# porcupine4v1_7.net
KiCad netlist of a schematic drawn in EAGLE
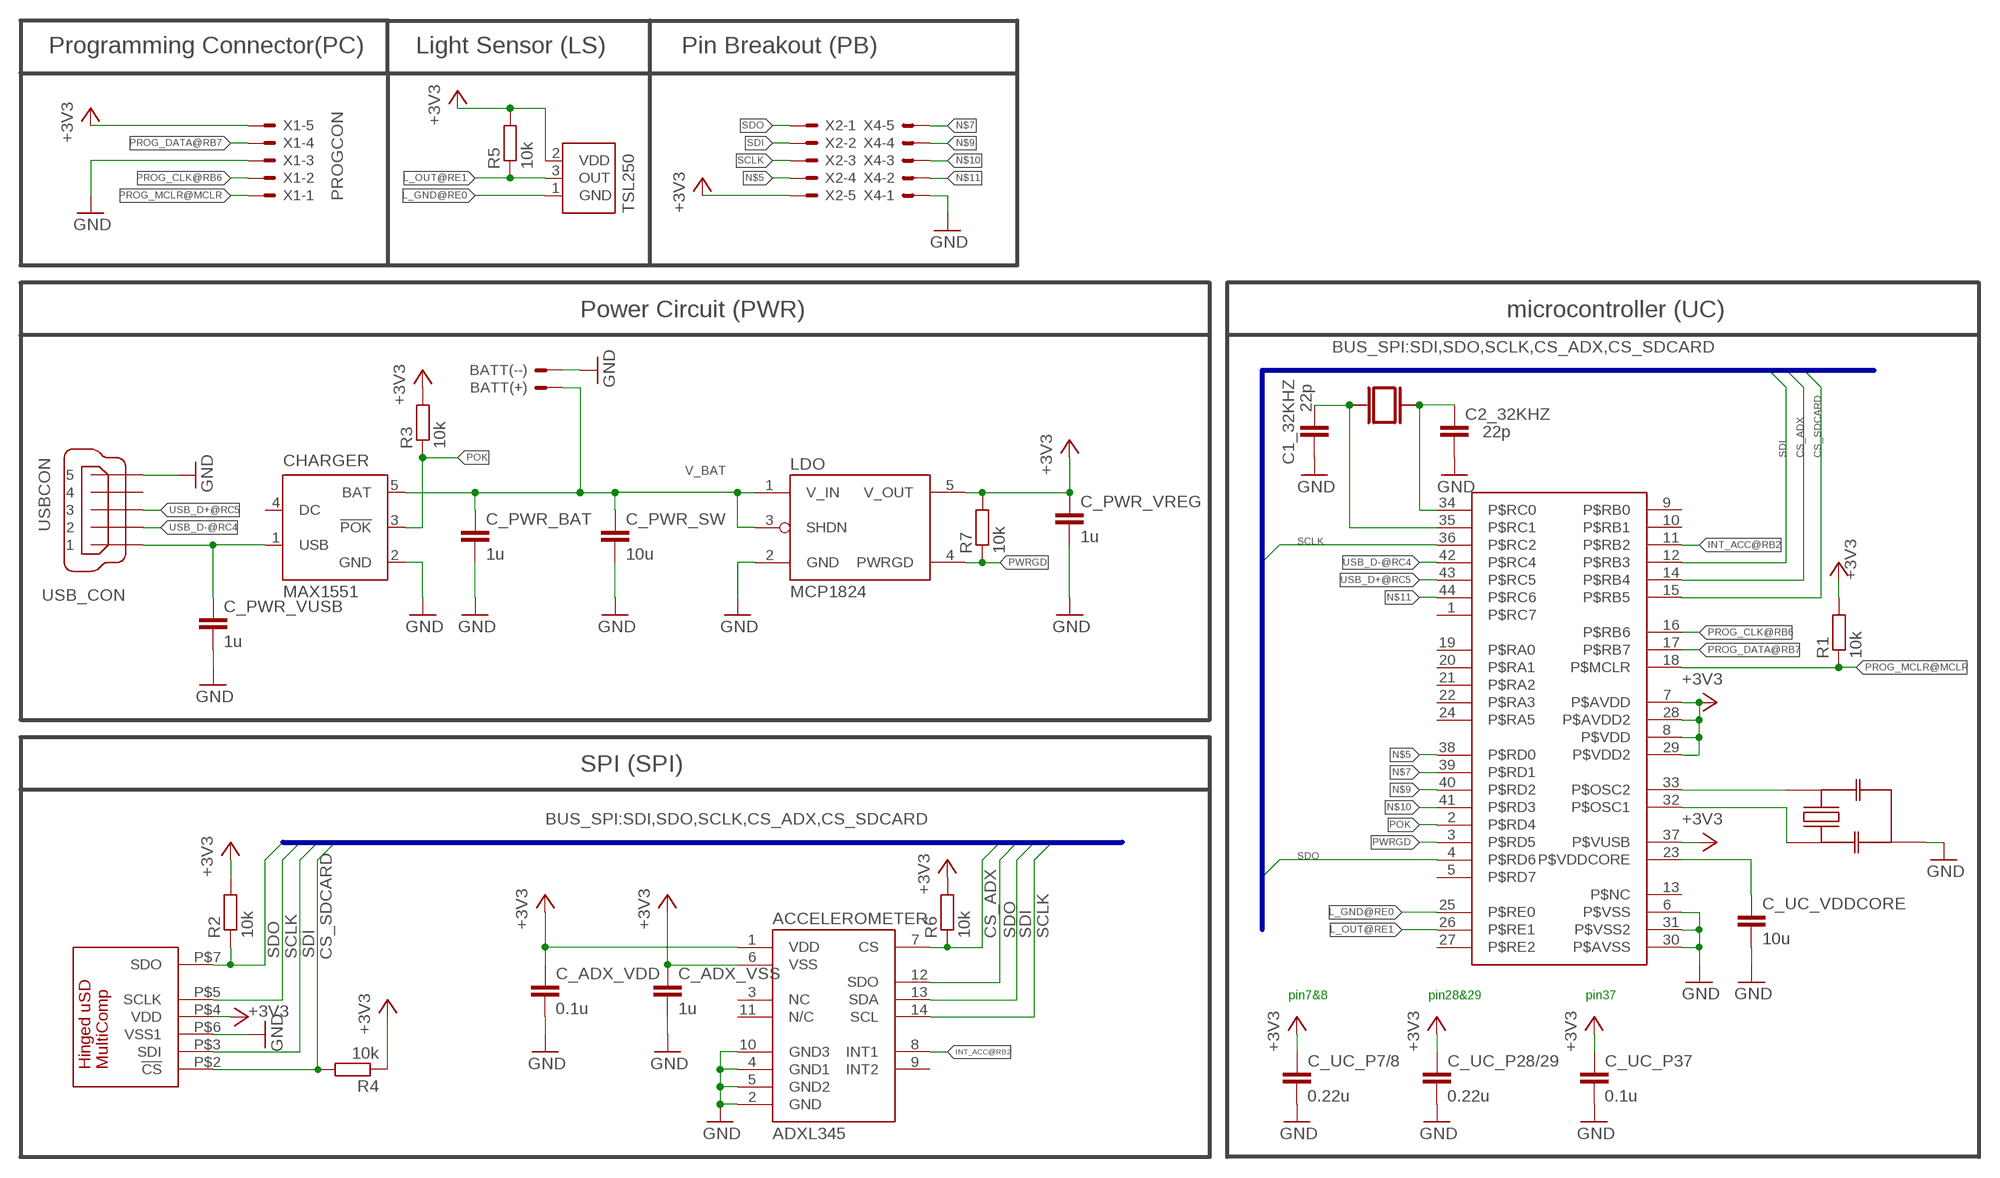
[diagram p0: schematic, sheet 1]

(export (version "E")
  (design (tool "Eeschema 10.0.6"))
  (components
    (comp (ref "12MHZ_RESONATOR")
      (value "RESONATORPRQC-S")
      (footprint "eagle-import:PRQC")
      (fields
        (field (name "DIGIKEY") "http://www.digikey.com/product-detail/en/PRQC12.00CR5010X000/478-6318-1-ND/2506334")
      )
      (libsource (lib "eagle-import") (part "RESONATORPRQC-S"))
    )
    (comp (ref "32KHZ_CRYSTAL")
      (value "SMD_CRYSTAL")
      (footprint "eagle-import:SMD_CRYSTAL")
      (libsource (lib "eagle-import") (part "SMD_CRYSTAL"))
    )
    (comp (ref "ACCELEROMETER")
      (value "ADXL345")
      (footprint "eagle-import:LGA14")
      (libsource (lib "eagle-import") (part "ADXL345"))
    )
    (comp (ref "BATT")
      (value "LI-ION-PACK")
      (footprint "eagle-import:LI-ION-CONNECT")
      (libsource (lib "eagle-import") (part "LI-ION-PACK"))
    )
    (comp (ref "C1_32KHZ")
      (value "22p")
      (footprint "eagle-import:C0603K")
      (libsource (lib "eagle-import") (part "C-EUC0603K"))
    )
    (comp (ref "C2_32KHZ")
      (value "22p")
      (footprint "eagle-import:C0603K")
      (libsource (lib "eagle-import") (part "C-EUC0603K"))
    )
    (comp (ref "CHARGER")
      (value "MAX1551")
      (footprint "eagle-import:SOT23-5L")
      (fields (field (name "MF") "MAXIM") (field (name "MPN") "MAX1551EZK-T"))
      (libsource (lib "eagle-import") (part "MAX1551"))
    )
    (comp (ref "C_ADX_VDD")
      (value "0.1u")
      (footprint "eagle-import:C0603K")
      (libsource (lib "eagle-import") (part "C-EUC0603K"))
    )
    (comp (ref "C_ADX_VSS")
      (value "1u")
      (footprint "eagle-import:C0603K")
      (libsource (lib "eagle-import") (part "C-EUC0603K"))
    )
    (comp (ref "C_PWR_BAT")
      (value "1u")
      (footprint "eagle-import:C0603K")
      (libsource (lib "eagle-import") (part "C-EUC0603K"))
    )
    (comp (ref "C_PWR_SW")
      (value "10u")
      (footprint "eagle-import:C0805K")
      (libsource (lib "eagle-import") (part "C-EUC0805K"))
    )
    (comp (ref "C_PWR_VREG")
      (value "1u")
      (footprint "eagle-import:C0603K")
      (libsource (lib "eagle-import") (part "C-EUC0603K"))
    )
    (comp (ref "C_PWR_VUSB")
      (value "1u")
      (footprint "eagle-import:C0603K")
      (libsource (lib "eagle-import") (part "C-EUC0603K"))
    )
    (comp (ref "C_UC_P7/8")
      (value "0.22u")
      (footprint "eagle-import:C0603K")
      (libsource (lib "eagle-import") (part "C-EUC0603K"))
    )
    (comp (ref "C_UC_P28/29")
      (value "0.22u")
      (footprint "eagle-import:C0603K")
      (libsource (lib "eagle-import") (part "C-EUC0603K"))
    )
    (comp (ref "C_UC_P37")
      (value "0.1u")
      (footprint "eagle-import:C0603K")
      (libsource (lib "eagle-import") (part "C-EUC0603K"))
    )
    (comp (ref "C_UC_VDDCORE")
      (value "10u")
      (footprint "eagle-import:C0805K")
      (libsource (lib "eagle-import") (part "C-EUC0805K"))
    )
    (comp (ref "LDO")
      (value "MCP1824")
      (footprint "eagle-import:SOT-23-5")
      (libsource (lib "eagle-import") (part "MCP1824"))
    )
    (comp (ref "LIGHTSENSE")
      (value "TSL250")
      (footprint "eagle-import:TSL")
      (libsource (lib "eagle-import") (part "TSL250"))
    )
    (comp (ref "PIC_CONTROLLER")
      (value "PIC_P2V6")
      (footprint "eagle-import:QFN44ML8X8")
      (libsource (lib "eagle-import") (part "PIC_P2V6"))
    )
    (comp (ref "R1")
      (value "10k")
      (footprint "eagle-import:R0603")
      (libsource (lib "eagle-import") (part "R-EU_R0603"))
    )
    (comp (ref "R2")
      (value "10k")
      (footprint "eagle-import:R0603")
      (libsource (lib "eagle-import") (part "R-EU_R0603"))
    )
    (comp (ref "R3")
      (value "10k")
      (footprint "eagle-import:R0603")
      (libsource (lib "eagle-import") (part "R-EU_R0603"))
    )
    (comp (ref "R4")
      (value "10k")
      (footprint "eagle-import:R0603")
      (libsource (lib "eagle-import") (part "R-EU_R0603"))
    )
    (comp (ref "R5")
      (value "10k")
      (footprint "eagle-import:R0603")
      (libsource (lib "eagle-import") (part "R-EU_R0603"))
    )
    (comp (ref "R6")
      (value "10k")
      (footprint "eagle-import:R0603")
      (libsource (lib "eagle-import") (part "R-EU_R0603"))
    )
    (comp (ref "R7")
      (value "10k")
      (footprint "eagle-import:R0603")
      (libsource (lib "eagle-import") (part "R-EU_R0603"))
    )
    (comp (ref "SDCARD_CON")
      (value "MICROSD_CONN")
      (footprint "eagle-import:460DA40013")
      (libsource (lib "eagle-import") (part "MICROSD_CONN"))
    )
    (comp (ref "USB_CON")
      (value "USBCON")
      (footprint "eagle-import:248601")
      (libsource (lib "eagle-import") (part "USBCON"))
    )
    (comp (ref "X1")
      (value "PROGCON")
      (footprint "eagle-import:53047-05-OCT")
      (libsource (lib "eagle-import") (part "PROGCON"))
    )
    (comp (ref "X2")
      (value "PROGCON")
      (footprint "eagle-import:53047-05-OCT")
      (libsource (lib "eagle-import") (part "PROGCON"))
    )
    (comp (ref "X4")
      (value "PROGCON")
      (footprint "eagle-import:53047-05-OCT")
      (libsource (lib "eagle-import") (part "PROGCON"))
    )
  )
  (nets
    (net (code "2") (name "+3V3") (class "Default")
      (node (ref "ACCELEROMETER") (pin "1") (pinfunction "VDD_1") (pintype "bidirectional"))
      (node (ref "ACCELEROMETER") (pin "6") (pinfunction "VSS_6") (pintype "bidirectional"))
      (node (ref "C_ADX_VDD") (pin "1") (pinfunction "1_1") (pintype "passive"))
      (node (ref "C_ADX_VSS") (pin "1") (pinfunction "1_1") (pintype "passive"))
      (node (ref "C_PWR_VREG") (pin "1") (pinfunction "1_1") (pintype "passive"))
      (node (ref "C_UC_P28/29") (pin "1") (pinfunction "1_1") (pintype "passive"))
      (node (ref "C_UC_P37") (pin "1") (pinfunction "1_1") (pintype "passive"))
      (node (ref "C_UC_P7/8") (pin "1") (pinfunction "1_1") (pintype "passive"))
      (node (ref "LDO") (pin "5") (pinfunction "V_OUT_5") (pintype "bidirectional"))
      (node (ref "LIGHTSENSE") (pin "2") (pinfunction "VDD_2") (pintype "power_in"))
      (node (ref "PIC_CONTROLLER") (pin "28") (pinfunction "P$AVDD2_28") (pintype "bidirectional"))
      (node (ref "PIC_CONTROLLER") (pin "29") (pinfunction "P$VDD2_29") (pintype "bidirectional"))
      (node (ref "PIC_CONTROLLER") (pin "37") (pinfunction "P$VUSB_37") (pintype "bidirectional"))
      (node (ref "PIC_CONTROLLER") (pin "7") (pinfunction "P$AVDD_7") (pintype "input"))
      (node (ref "PIC_CONTROLLER") (pin "8") (pinfunction "P$VDD_8") (pintype "bidirectional"))
      (node (ref "R1") (pin "2") (pinfunction "2_2") (pintype "passive"))
      (node (ref "R2") (pin "2") (pinfunction "2_2") (pintype "passive"))
      (node (ref "R3") (pin "2") (pinfunction "2_2") (pintype "passive"))
      (node (ref "R4") (pin "1") (pinfunction "1_1") (pintype "passive"))
      (node (ref "R5") (pin "2") (pinfunction "2_2") (pintype "passive"))
      (node (ref "R6") (pin "2") (pinfunction "2_2") (pintype "passive"))
      (node (ref "R7") (pin "2") (pinfunction "2_2") (pintype "passive"))
      (node (ref "SDCARD_CON") (pin "P$4") (pinfunction "VDD_P$4") (pintype "bidirectional"))
      (node (ref "X1") (pin "5") (pinfunction "S_5") (pintype "passive"))
      (node (ref "X2") (pin "5") (pinfunction "S_5") (pintype "passive"))
    )
    (net (code "3") (name "/CS_ADX") (class "Default")
      (node (ref "ACCELEROMETER") (pin "7") (pinfunction "CS_7") (pintype "bidirectional"))
      (node (ref "PIC_CONTROLLER") (pin "14") (pinfunction "P$RB4_14") (pintype "bidirectional"))
      (node (ref "R6") (pin "1") (pinfunction "1_1") (pintype "passive"))
    )
    (net (code "4") (name "/CS_SDCARD") (class "Default")
      (node (ref "PIC_CONTROLLER") (pin "15") (pinfunction "P$RB5_15") (pintype "bidirectional"))
      (node (ref "R4") (pin "2") (pinfunction "2_2") (pintype "passive"))
      (node (ref "SDCARD_CON") (pin "P$2") (pinfunction "~{CS}_P$2") (pintype "bidirectional"))
    )
    (net (code "5") (name "/P$RD7") (class "Default")
      (node (ref "PIC_CONTROLLER") (pin "5") (pinfunction "P$RD7_5") (pintype "power_in"))
    )
    (net (code "6") (name "/V_BAT") (class "Default")
      (node (ref "BATT") (pin "1") (pinfunction "S_1") (pintype "passive"))
      (node (ref "CHARGER") (pin "5") (pinfunction "BAT_5") (pintype "passive"))
      (node (ref "C_PWR_BAT") (pin "1") (pinfunction "1_1") (pintype "passive"))
      (node (ref "C_PWR_SW") (pin "1") (pinfunction "1_1") (pintype "passive"))
      (node (ref "LDO") (pin "1") (pinfunction "V_IN_1") (pintype "bidirectional"))
      (node (ref "LDO") (pin "3") (pinfunction "SHDN_3") (pintype "bidirectional"))
    )
    (net (code "8") (name "GND") (class "Default")
      (node (ref "12MHZ_RESONATOR") (pin "GND") (pinfunction "GND_GND") (pintype "bidirectional"))
      (node (ref "ACCELEROMETER") (pin "10") (pinfunction "GND3_10") (pintype "bidirectional"))
      (node (ref "ACCELEROMETER") (pin "2") (pinfunction "GND_2") (pintype "bidirectional"))
      (node (ref "ACCELEROMETER") (pin "4") (pinfunction "GND1_4") (pintype "bidirectional"))
      (node (ref "ACCELEROMETER") (pin "5") (pinfunction "GND2_5") (pintype "bidirectional"))
      (node (ref "BATT") (pin "2") (pinfunction "S_2") (pintype "passive"))
      (node (ref "C1_32KHZ") (pin "2") (pinfunction "2_2") (pintype "passive"))
      (node (ref "C2_32KHZ") (pin "2") (pinfunction "2_2") (pintype "passive"))
      (node (ref "CHARGER") (pin "2") (pinfunction "GND_2") (pintype "power_in"))
      (node (ref "C_ADX_VDD") (pin "2") (pinfunction "2_2") (pintype "passive"))
      (node (ref "C_ADX_VSS") (pin "2") (pinfunction "2_2") (pintype "passive"))
      (node (ref "C_PWR_BAT") (pin "2") (pinfunction "2_2") (pintype "passive"))
      (node (ref "C_PWR_SW") (pin "2") (pinfunction "2_2") (pintype "passive"))
      (node (ref "C_PWR_VREG") (pin "2") (pinfunction "2_2") (pintype "passive"))
      (node (ref "C_PWR_VUSB") (pin "2") (pinfunction "2_2") (pintype "passive"))
      (node (ref "C_UC_P28/29") (pin "2") (pinfunction "2_2") (pintype "passive"))
      (node (ref "C_UC_P37") (pin "2") (pinfunction "2_2") (pintype "passive"))
      (node (ref "C_UC_P7/8") (pin "2") (pinfunction "2_2") (pintype "passive"))
      (node (ref "C_UC_VDDCORE") (pin "2") (pinfunction "2_2") (pintype "passive"))
      (node (ref "LDO") (pin "2") (pinfunction "GND_2") (pintype "bidirectional"))
      (node (ref "PIC_CONTROLLER") (pin "30") (pinfunction "P$AVSS_30") (pintype "input"))
      (node (ref "PIC_CONTROLLER") (pin "31") (pinfunction "P$VSS2_31") (pintype "output"))
      (node (ref "PIC_CONTROLLER") (pin "6") (pinfunction "P$VSS_6") (pintype "input"))
      (node (ref "SDCARD_CON") (pin "P$6") (pinfunction "VSS1_P$6") (pintype "bidirectional"))
      (node (ref "USB_CON") (pin "5") (pinfunction "5_5") (pintype "input"))
      (node (ref "X1") (pin "3") (pinfunction "S_3") (pintype "passive"))
      (node (ref "X4") (pin "1") (pinfunction "S_1") (pintype "passive"))
    )
    (net (code "9") (name "INT_ACC@RB2") (class "Default")
      (node (ref "ACCELEROMETER") (pin "8") (pinfunction "INT1_8") (pintype "bidirectional"))
      (node (ref "PIC_CONTROLLER") (pin "11") (pinfunction "P$RB2_11") (pintype "power_in"))
    )
    (net (code "10") (name "L_GND@RE0") (class "Default")
      (node (ref "LIGHTSENSE") (pin "1") (pinfunction "GND_1") (pintype "power_in"))
      (node (ref "PIC_CONTROLLER") (pin "25") (pinfunction "P$RE0_25") (pintype "bidirectional"))
    )
    (net (code "11") (name "L_OUT@RE1") (class "Default")
      (node (ref "LIGHTSENSE") (pin "3") (pinfunction "OUT_3") (pintype "output"))
      (node (ref "PIC_CONTROLLER") (pin "26") (pinfunction "P$RE1_26") (pintype "input"))
      (node (ref "R5") (pin "1") (pinfunction "1_1") (pintype "passive"))
    )
    (net (code "12") (name "N$5") (class "Default")
      (node (ref "PIC_CONTROLLER") (pin "38") (pinfunction "P$RD0_38") (pintype "bidirectional"))
      (node (ref "X2") (pin "4") (pinfunction "S_4") (pintype "passive"))
    )
    (net (code "13") (name "N$7") (class "Default")
      (node (ref "PIC_CONTROLLER") (pin "39") (pinfunction "P$RD1_39") (pintype "bidirectional"))
      (node (ref "X4") (pin "5") (pinfunction "S_5") (pintype "passive"))
    )
    (net (code "14") (name "N$9") (class "Default")
      (node (ref "PIC_CONTROLLER") (pin "40") (pinfunction "P$RD2_40") (pintype "bidirectional"))
      (node (ref "X4") (pin "4") (pinfunction "S_4") (pintype "passive"))
    )
    (net (code "15") (name "N$10") (class "Default")
      (node (ref "PIC_CONTROLLER") (pin "41") (pinfunction "P$RD3_41") (pintype "bidirectional"))
      (node (ref "X4") (pin "3") (pinfunction "S_3") (pintype "passive"))
    )
    (net (code "16") (name "N$11") (class "Default")
      (node (ref "PIC_CONTROLLER") (pin "44") (pinfunction "P$RC6_44") (pintype "bidirectional"))
      (node (ref "X4") (pin "2") (pinfunction "S_2") (pintype "passive"))
    )
    (net (code "17") (name "Net-(32KHZ_CRYSTAL-1)") (class "Default")
      (node (ref "32KHZ_CRYSTAL") (pin "P$1") (pinfunction "1_P$1") (pintype "passive"))
      (node (ref "C1_32KHZ") (pin "1") (pinfunction "1_1") (pintype "passive"))
      (node (ref "PIC_CONTROLLER") (pin "35") (pinfunction "P$RC1_35") (pintype "bidirectional"))
    )
    (net (code "18") (name "Net-(32KHZ_CRYSTAL-2)") (class "Default")
      (node (ref "32KHZ_CRYSTAL") (pin "P$2") (pinfunction "2_P$2") (pintype "passive"))
      (node (ref "C2_32KHZ") (pin "1") (pinfunction "1_1") (pintype "passive"))
      (node (ref "PIC_CONTROLLER") (pin "34") (pinfunction "P$RC0_34") (pintype "bidirectional"))
    )
    (net (code "19") (name "Net-(CHARGER-USB)") (class "Default")
      (node (ref "CHARGER") (pin "1") (pinfunction "USB_1") (pintype "input"))
      (node (ref "C_PWR_VUSB") (pin "1") (pinfunction "1_1") (pintype "passive"))
      (node (ref "USB_CON") (pin "1") (pinfunction "1_1") (pintype "input"))
    )
    (net (code "20") (name "Net-(PIC_CONTROLLER-P$OSC1)") (class "Default")
      (node (ref "12MHZ_RESONATOR") (pin "2") (pinfunction "2_2") (pintype "bidirectional"))
      (node (ref "PIC_CONTROLLER") (pin "32") (pinfunction "P$OSC1_32") (pintype "bidirectional"))
    )
    (net (code "21") (name "Net-(PIC_CONTROLLER-P$OSC2)") (class "Default")
      (node (ref "12MHZ_RESONATOR") (pin "1") (pinfunction "1_1") (pintype "bidirectional"))
      (node (ref "PIC_CONTROLLER") (pin "33") (pinfunction "P$OSC2_33") (pintype "bidirectional"))
    )
    (net (code "22") (name "Net-(PIC_CONTROLLER-P$VDDCORE)") (class "Default")
      (node (ref "C_UC_VDDCORE") (pin "1") (pinfunction "1_1") (pintype "passive"))
      (node (ref "PIC_CONTROLLER") (pin "23") (pinfunction "P$VDDCORE_23") (pintype "bidirectional"))
    )
    (net (code "23") (name "POK") (class "Default")
      (node (ref "CHARGER") (pin "3") (pinfunction "~{POK}_3") (pintype "output"))
      (node (ref "PIC_CONTROLLER") (pin "2") (pinfunction "P$RD4_2") (pintype "bidirectional"))
      (node (ref "R3") (pin "1") (pinfunction "1_1") (pintype "passive"))
    )
    (net (code "24") (name "PROG_CLK@RB6") (class "Default")
      (node (ref "PIC_CONTROLLER") (pin "16") (pinfunction "P$RB6_16") (pintype "power_in"))
      (node (ref "X1") (pin "2") (pinfunction "S_2") (pintype "passive"))
    )
    (net (code "25") (name "PROG_DATA@RB7") (class "Default")
      (node (ref "PIC_CONTROLLER") (pin "17") (pinfunction "P$RB7_17") (pintype "power_in"))
      (node (ref "X1") (pin "4") (pinfunction "S_4") (pintype "passive"))
    )
    (net (code "26") (name "PROG_MCLR@MCLR") (class "Default")
      (node (ref "PIC_CONTROLLER") (pin "18") (pinfunction "P$MCLR_18") (pintype "input"))
      (node (ref "R1") (pin "1") (pinfunction "1_1") (pintype "passive"))
      (node (ref "X1") (pin "1") (pinfunction "S_1") (pintype "passive"))
    )
    (net (code "27") (name "PWRGD") (class "Default")
      (node (ref "LDO") (pin "4") (pinfunction "PWRGD_4") (pintype "bidirectional"))
      (node (ref "PIC_CONTROLLER") (pin "3") (pinfunction "P$RD5_3") (pintype "power_in"))
      (node (ref "R7") (pin "1") (pinfunction "1_1") (pintype "passive"))
    )
    (net (code "28") (name "SCLK") (class "Default")
      (node (ref "ACCELEROMETER") (pin "14") (pinfunction "SCL_14") (pintype "bidirectional"))
      (node (ref "PIC_CONTROLLER") (pin "36") (pinfunction "P$RC2_36") (pintype "bidirectional"))
      (node (ref "SDCARD_CON") (pin "P$5") (pinfunction "SCLK_P$5") (pintype "bidirectional"))
      (node (ref "X2") (pin "3") (pinfunction "S_3") (pintype "passive"))
    )
    (net (code "29") (name "SDI") (class "Default")
      (node (ref "ACCELEROMETER") (pin "13") (pinfunction "SDA_13") (pintype "bidirectional"))
      (node (ref "PIC_CONTROLLER") (pin "12") (pinfunction "P$RB3_12") (pintype "bidirectional"))
      (node (ref "SDCARD_CON") (pin "P$3") (pinfunction "SDI_P$3") (pintype "bidirectional"))
      (node (ref "X2") (pin "2") (pinfunction "S_2") (pintype "passive"))
    )
    (net (code "30") (name "SDO") (class "Default")
      (node (ref "ACCELEROMETER") (pin "12") (pinfunction "SDO_12") (pintype "bidirectional"))
      (node (ref "PIC_CONTROLLER") (pin "4") (pinfunction "P$RD6_4") (pintype "bidirectional"))
      (node (ref "R2") (pin "1") (pinfunction "1_1") (pintype "passive"))
      (node (ref "SDCARD_CON") (pin "P$7") (pinfunction "SDO_P$7") (pintype "bidirectional"))
      (node (ref "X2") (pin "1") (pinfunction "S_1") (pintype "passive"))
    )
    (net (code "31") (name "USB_D+@RC5") (class "Default")
      (node (ref "PIC_CONTROLLER") (pin "43") (pinfunction "P$RC5_43") (pintype "bidirectional"))
      (node (ref "USB_CON") (pin "3") (pinfunction "3_3") (pintype "input"))
    )
    (net (code "32") (name "USB_D-@RC4") (class "Default")
      (node (ref "PIC_CONTROLLER") (pin "42") (pinfunction "P$RC4_42") (pintype "bidirectional"))
      (node (ref "USB_CON") (pin "2") (pinfunction "2_2") (pintype "input"))
    )
    (net (code "33") (name "unconnected-(ACCELEROMETER-INT2-Pad9)") (class "Default")
      (node (ref "ACCELEROMETER") (pin "9") (pinfunction "INT2_9") (pintype "bidirectional"))
    )
    (net (code "34") (name "unconnected-(ACCELEROMETER-NC-Pad3)") (class "Default")
      (node (ref "ACCELEROMETER") (pin "3") (pinfunction "NC_3") (pintype "bidirectional"))
    )
    (net (code "35") (name "unconnected-(ACCELEROMETER-N{slash}C-Pad11)") (class "Default")
      (node (ref "ACCELEROMETER") (pin "11") (pinfunction "N/C_11") (pintype "bidirectional"))
    )
    (net (code "36") (name "unconnected-(CHARGER-DC-Pad4)") (class "Default")
      (node (ref "CHARGER") (pin "4") (pinfunction "DC_4") (pintype "input"))
    )
    (net (code "37") (name "unconnected-(PIC_CONTROLLER-P$NC-Pad13)") (class "Default")
      (node (ref "PIC_CONTROLLER") (pin "13") (pinfunction "P$NC_13") (pintype "bidirectional"))
    )
    (net (code "38") (name "unconnected-(PIC_CONTROLLER-P$RA0-Pad19)") (class "Default")
      (node (ref "PIC_CONTROLLER") (pin "19") (pinfunction "P$RA0_19") (pintype "bidirectional"))
    )
    (net (code "39") (name "unconnected-(PIC_CONTROLLER-P$RA1-Pad20)") (class "Default")
      (node (ref "PIC_CONTROLLER") (pin "20") (pinfunction "P$RA1_20") (pintype "bidirectional"))
    )
    (net (code "40") (name "unconnected-(PIC_CONTROLLER-P$RA2-Pad21)") (class "Default")
      (node (ref "PIC_CONTROLLER") (pin "21") (pinfunction "P$RA2_21") (pintype "bidirectional"))
    )
    (net (code "41") (name "unconnected-(PIC_CONTROLLER-P$RA3-Pad22)") (class "Default")
      (node (ref "PIC_CONTROLLER") (pin "22") (pinfunction "P$RA3_22") (pintype "bidirectional"))
    )
    (net (code "42") (name "unconnected-(PIC_CONTROLLER-P$RA5-Pad24)") (class "Default")
      (node (ref "PIC_CONTROLLER") (pin "24") (pinfunction "P$RA5_24") (pintype "bidirectional"))
    )
    (net (code "43") (name "unconnected-(PIC_CONTROLLER-P$RB0-Pad9)") (class "Default")
      (node (ref "PIC_CONTROLLER") (pin "9") (pinfunction "P$RB0_9") (pintype "bidirectional"))
    )
    (net (code "44") (name "unconnected-(PIC_CONTROLLER-P$RB1-Pad10)") (class "Default")
      (node (ref "PIC_CONTROLLER") (pin "10") (pinfunction "P$RB1_10") (pintype "bidirectional"))
    )
    (net (code "45") (name "unconnected-(PIC_CONTROLLER-P$RC7-Pad1)") (class "Default")
      (node (ref "PIC_CONTROLLER") (pin "1") (pinfunction "P$RC7_1") (pintype "bidirectional"))
    )
    (net (code "46") (name "unconnected-(PIC_CONTROLLER-P$RE2-Pad27)") (class "Default")
      (node (ref "PIC_CONTROLLER") (pin "27") (pinfunction "P$RE2_27") (pintype "bidirectional"))
    )
    (net (code "47") (name "unconnected-(USB_CON-Pad4)") (class "Default")
      (node (ref "USB_CON") (pin "4") (pinfunction "4_4") (pintype "input"))
    )
  )
)
